# MainBoard_Interface_ProyimityDetector.net
KiCad netlist of a schematic drawn in Altium Designer
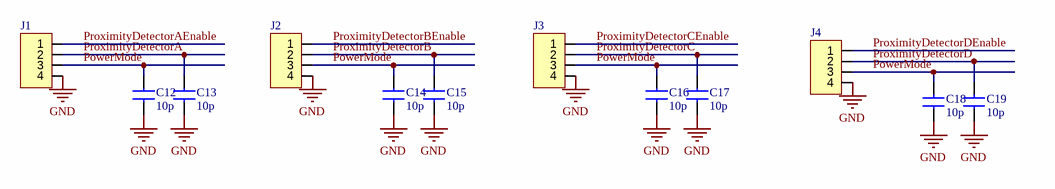
[diagram p0: MainBoard_Interface_ProyimityDetector.SchDoc]

(export (version "E")
  (design (tool "Eeschema 10.0.6"))
  (components
    (comp (ref "C12")
      (value "10p")
      (footprint "0805_C")
      (description "Normaler Kondensator")
      (libsource (lib "MainBoard") (part "C?"))
    )
    (comp (ref "C13")
      (value "10p")
      (footprint "0805_C")
      (description "Normaler Kondensator")
      (libsource (lib "MainBoard") (part "C?"))
    )
    (comp (ref "C14")
      (value "10p")
      (footprint "0805_C")
      (description "Normaler Kondensator")
      (libsource (lib "MainBoard") (part "C?"))
    )
    (comp (ref "C15")
      (value "10p")
      (footprint "0805_C")
      (description "Normaler Kondensator")
      (libsource (lib "MainBoard") (part "C?"))
    )
    (comp (ref "C16")
      (value "10p")
      (footprint "0805_C")
      (description "Normaler Kondensator")
      (libsource (lib "MainBoard") (part "C?"))
    )
    (comp (ref "C17")
      (value "10p")
      (footprint "0805_C")
      (description "Normaler Kondensator")
      (libsource (lib "MainBoard") (part "C?"))
    )
    (comp (ref "C18")
      (value "10p")
      (footprint "0805_C")
      (description "Normaler Kondensator")
      (libsource (lib "MainBoard") (part "C?"))
    )
    (comp (ref "C19")
      (value "10p")
      (footprint "0805_C")
      (description "Normaler Kondensator")
      (libsource (lib "MainBoard") (part "C?"))
    )
    (comp (ref "J1") (value "~") (footprint "CON_THT_4P_RM2.54") (libsource (lib "Sch_Lib") (part "CON_4P")))
    (comp (ref "J2") (value "~") (footprint "CON_THT_4P_RM2.54") (libsource (lib "Sch_Lib") (part "CON_4P")))
    (comp (ref "J3") (value "~") (footprint "CON_THT_4P_RM2.54") (libsource (lib "Sch_Lib") (part "CON_4P")))
    (comp (ref "J4") (value "~") (footprint "CON_THT_4P_RM2.54") (libsource (lib "Sch_Lib") (part "CON_4P")))
  )
  (nets
    (net (code "1") (name "/PowerMode") (class "Default")
      (node (ref "C12") (pin "2") (pinfunction "2_2") (pintype "passive"))
      (node (ref "C14") (pin "2") (pinfunction "2_2") (pintype "passive"))
      (node (ref "C16") (pin "2") (pinfunction "2_2") (pintype "passive"))
      (node (ref "C18") (pin "2") (pinfunction "2_2") (pintype "passive"))
      (node (ref "J1") (pin "3") (pinfunction "3_3") (pintype "passive"))
      (node (ref "J2") (pin "3") (pinfunction "3_3") (pintype "passive"))
      (node (ref "J3") (pin "3") (pinfunction "3_3") (pintype "passive"))
      (node (ref "J4") (pin "3") (pinfunction "3_3") (pintype "passive"))
    )
    (net (code "2") (name "/ProximityDetectorA") (class "Default")
      (node (ref "C13") (pin "2") (pinfunction "2_2") (pintype "passive"))
      (node (ref "J1") (pin "2") (pinfunction "2_2") (pintype "passive"))
    )
    (net (code "3") (name "/ProximityDetectorAEnable") (class "Default")
      (node (ref "J1") (pin "1") (pinfunction "1_1") (pintype "passive"))
    )
    (net (code "4") (name "/ProximityDetectorB") (class "Default")
      (node (ref "C15") (pin "2") (pinfunction "2_2") (pintype "passive"))
      (node (ref "J2") (pin "2") (pinfunction "2_2") (pintype "passive"))
    )
    (net (code "5") (name "/ProximityDetectorBEnable") (class "Default")
      (node (ref "J2") (pin "1") (pinfunction "1_1") (pintype "passive"))
    )
    (net (code "6") (name "/ProximityDetectorC") (class "Default")
      (node (ref "C17") (pin "2") (pinfunction "2_2") (pintype "passive"))
      (node (ref "J3") (pin "2") (pinfunction "2_2") (pintype "passive"))
    )
    (net (code "7") (name "/ProximityDetectorCEnable") (class "Default")
      (node (ref "J3") (pin "1") (pinfunction "1_1") (pintype "passive"))
    )
    (net (code "8") (name "/ProximityDetectorD") (class "Default")
      (node (ref "C19") (pin "2") (pinfunction "2_2") (pintype "passive"))
      (node (ref "J4") (pin "2") (pinfunction "2_2") (pintype "passive"))
    )
    (net (code "9") (name "/ProximityDetectorDEnable") (class "Default")
      (node (ref "J4") (pin "1") (pinfunction "1_1") (pintype "passive"))
    )
    (net (code "10") (name "GND") (class "Default")
      (node (ref "C12") (pin "1") (pinfunction "1_1") (pintype "passive"))
      (node (ref "C13") (pin "1") (pinfunction "1_1") (pintype "passive"))
      (node (ref "C14") (pin "1") (pinfunction "1_1") (pintype "passive"))
      (node (ref "C15") (pin "1") (pinfunction "1_1") (pintype "passive"))
      (node (ref "C16") (pin "1") (pinfunction "1_1") (pintype "passive"))
      (node (ref "C17") (pin "1") (pinfunction "1_1") (pintype "passive"))
      (node (ref "C18") (pin "1") (pinfunction "1_1") (pintype "passive"))
      (node (ref "C19") (pin "1") (pinfunction "1_1") (pintype "passive"))
      (node (ref "J1") (pin "4") (pinfunction "4_4") (pintype "passive"))
      (node (ref "J2") (pin "4") (pinfunction "4_4") (pintype "passive"))
      (node (ref "J3") (pin "4") (pinfunction "4_4") (pintype "passive"))
      (node (ref "J4") (pin "4") (pinfunction "4_4") (pintype "passive"))
    )
  )
)
